# InfoAmazonia.net
KiCad netlist of a schematic drawn in EAGLE
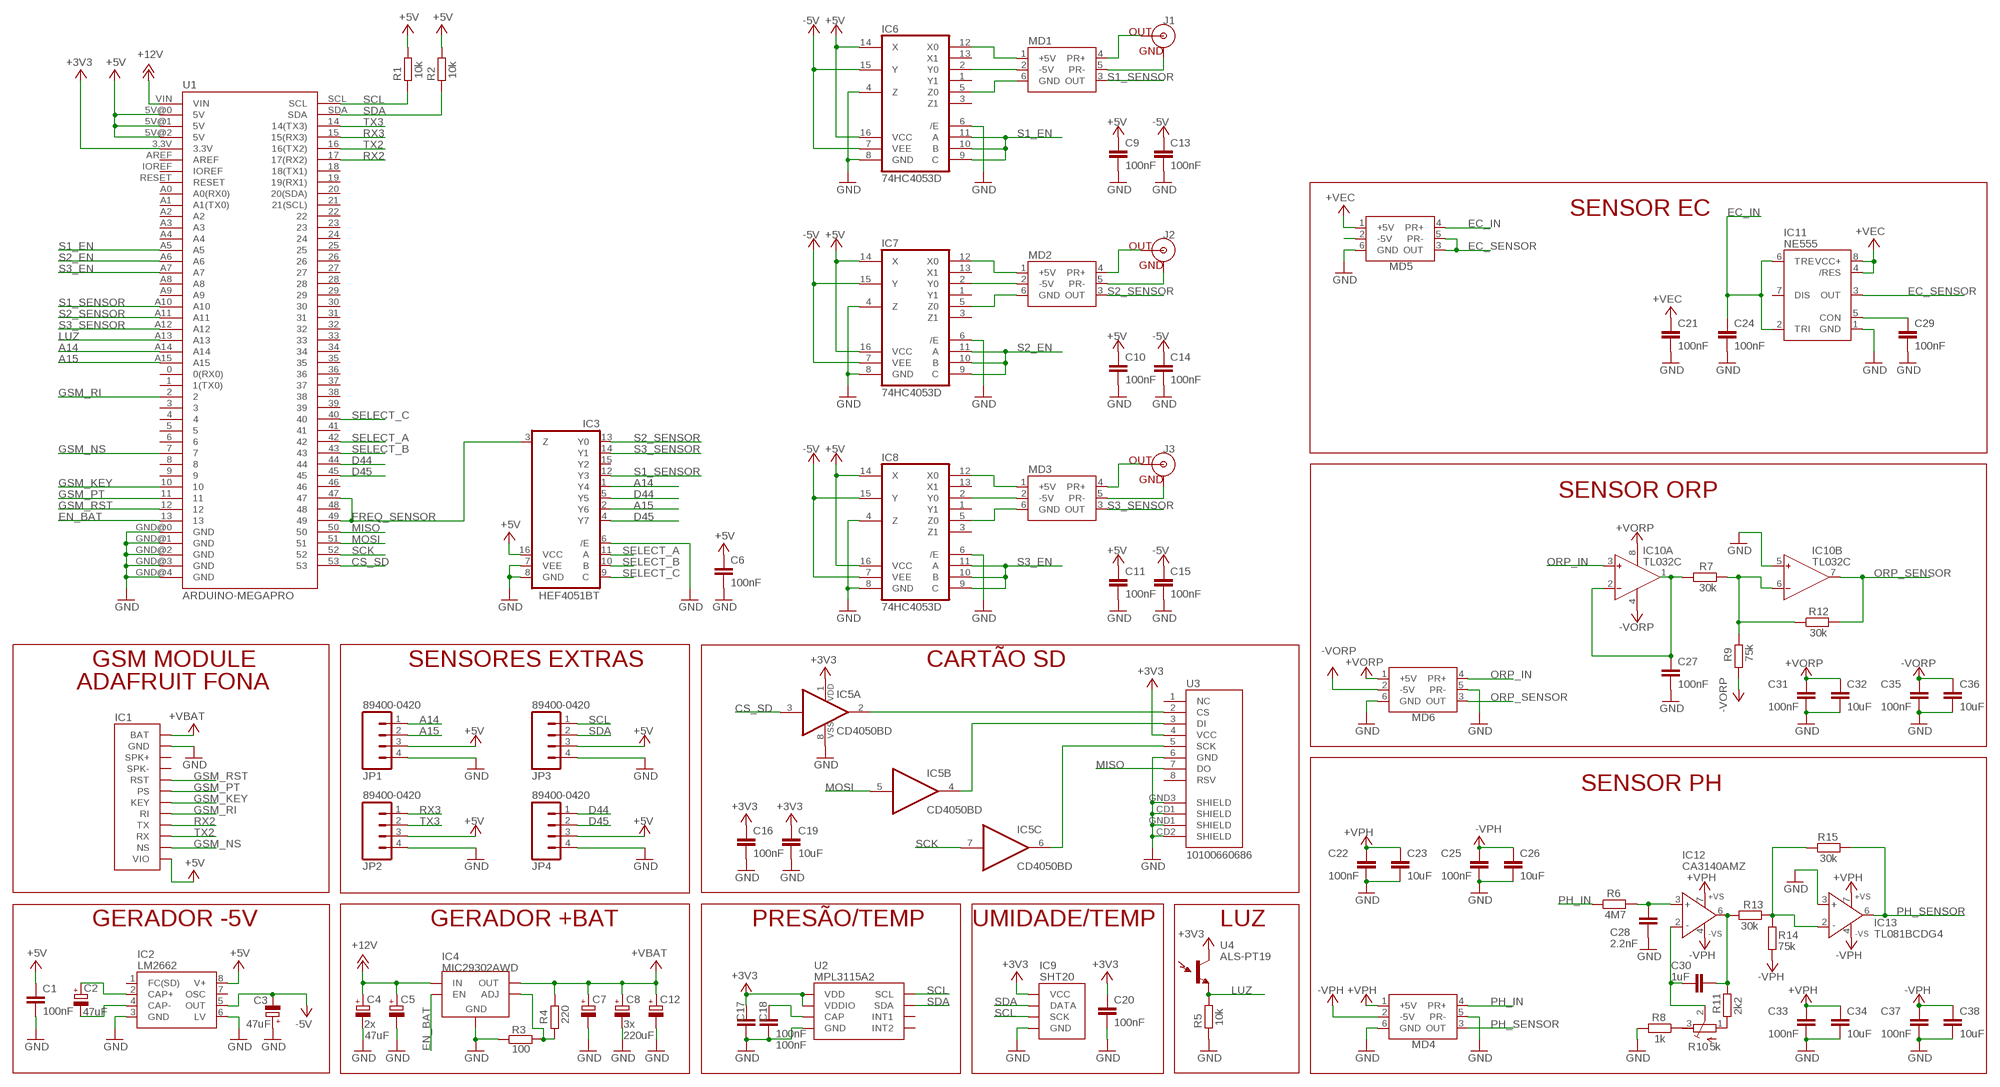
[diagram p0: schematic, sheet 1]

(export (version "E")
  (design (tool "Eeschema 10.0.6"))
  (components
    (comp (ref "C1")
      (value "100nF")
      (footprint "eagle-import:C0603")
      (libsource (lib "eagle-import") (part "C-EUC0603"))
    )
    (comp (ref "C2")
      (value "47uF")
      (footprint "eagle-import:SMC_B")
      (libsource (lib "eagle-import") (part "CPOL-EUSMC_B"))
    )
    (comp (ref "C3")
      (value "47uF")
      (footprint "eagle-import:SMC_B")
      (libsource (lib "eagle-import") (part "CPOL-EUSMC_B"))
    )
    (comp (ref "C4")
      (value "47uF")
      (footprint "eagle-import:UD-6,3X5,8_NICHICON")
      (libsource (lib "eagle-import") (part "CPOL-EUUD6,3-5,8"))
    )
    (comp (ref "C5")
      (value "47uF")
      (footprint "eagle-import:UD-6,3X5,8_NICHICON")
      (libsource (lib "eagle-import") (part "CPOL-EUUD6,3-5,8"))
    )
    (comp (ref "C6")
      (value "100nF")
      (footprint "eagle-import:C0603")
      (libsource (lib "eagle-import") (part "C-EUC0603"))
    )
    (comp (ref "C7")
      (value "220uF")
      (footprint "eagle-import:UD-6,3X5,8_NICHICON")
      (libsource (lib "eagle-import") (part "CPOL-EUUD6,3-5,8"))
    )
    (comp (ref "C8")
      (value "220uF")
      (footprint "eagle-import:UD-6,3X5,8_NICHICON")
      (libsource (lib "eagle-import") (part "CPOL-EUUD6,3-5,8"))
    )
    (comp (ref "C9")
      (value "100nF")
      (footprint "eagle-import:C0603")
      (libsource (lib "eagle-import") (part "C-EUC0603"))
    )
    (comp (ref "C10")
      (value "100nF")
      (footprint "eagle-import:C0603")
      (libsource (lib "eagle-import") (part "C-EUC0603"))
    )
    (comp (ref "C11")
      (value "100nF")
      (footprint "eagle-import:C0603")
      (libsource (lib "eagle-import") (part "C-EUC0603"))
    )
    (comp (ref "C12")
      (value "220uF")
      (footprint "eagle-import:UD-6,3X5,8_NICHICON")
      (libsource (lib "eagle-import") (part "CPOL-EUUD6,3-5,8"))
    )
    (comp (ref "C13")
      (value "100nF")
      (footprint "eagle-import:C0603")
      (libsource (lib "eagle-import") (part "C-EUC0603"))
    )
    (comp (ref "C14")
      (value "100nF")
      (footprint "eagle-import:C0603")
      (libsource (lib "eagle-import") (part "C-EUC0603"))
    )
    (comp (ref "C15")
      (value "100nF")
      (footprint "eagle-import:C0603")
      (libsource (lib "eagle-import") (part "C-EUC0603"))
    )
    (comp (ref "C16")
      (value "100nF")
      (footprint "eagle-import:C0603")
      (libsource (lib "eagle-import") (part "C-EUC0603"))
    )
    (comp (ref "C17")
      (value "100nF")
      (footprint "eagle-import:C0603")
      (libsource (lib "eagle-import") (part "C-EUC0603"))
    )
    (comp (ref "C18")
      (value "100nF")
      (footprint "eagle-import:C0603")
      (libsource (lib "eagle-import") (part "C-EUC0603"))
    )
    (comp (ref "C19")
      (value "10uF")
      (footprint "eagle-import:C0603")
      (libsource (lib "eagle-import") (part "C-EUC0603"))
    )
    (comp (ref "C20")
      (value "100nF")
      (footprint "eagle-import:C0603")
      (libsource (lib "eagle-import") (part "C-EUC0603"))
    )
    (comp (ref "C21")
      (value "100nF")
      (footprint "eagle-import:C0603")
      (libsource (lib "eagle-import") (part "C-EUC0603"))
    )
    (comp (ref "C22")
      (value "100nF")
      (footprint "eagle-import:C0603")
      (libsource (lib "eagle-import") (part "C-EUC0603"))
    )
    (comp (ref "C23")
      (value "10uF")
      (footprint "eagle-import:C0603")
      (libsource (lib "eagle-import") (part "C-EUC0603"))
    )
    (comp (ref "C24")
      (value "100nF")
      (footprint "eagle-import:C0603")
      (libsource (lib "eagle-import") (part "C-EUC0603"))
    )
    (comp (ref "C25")
      (value "100nF")
      (footprint "eagle-import:C0603")
      (libsource (lib "eagle-import") (part "C-EUC0603"))
    )
    (comp (ref "C26")
      (value "10uF")
      (footprint "eagle-import:C0603")
      (libsource (lib "eagle-import") (part "C-EUC0603"))
    )
    (comp (ref "C27")
      (value "100nF")
      (footprint "eagle-import:C0603")
      (libsource (lib "eagle-import") (part "C-EUC0603"))
    )
    (comp (ref "C28")
      (value "2.2nF")
      (footprint "eagle-import:C0603")
      (libsource (lib "eagle-import") (part "C-EUC0603"))
    )
    (comp (ref "C29")
      (value "100nF")
      (footprint "eagle-import:C0603")
      (libsource (lib "eagle-import") (part "C-EUC0603"))
    )
    (comp (ref "C30")
      (value "1uF")
      (footprint "eagle-import:C0603")
      (libsource (lib "eagle-import") (part "C-EUC0603"))
    )
    (comp (ref "C31")
      (value "100nF")
      (footprint "eagle-import:C0603")
      (libsource (lib "eagle-import") (part "C-EUC0603"))
    )
    (comp (ref "C32")
      (value "10uF")
      (footprint "eagle-import:C0603")
      (libsource (lib "eagle-import") (part "C-EUC0603"))
    )
    (comp (ref "C33")
      (value "100nF")
      (footprint "eagle-import:C0603")
      (libsource (lib "eagle-import") (part "C-EUC0603"))
    )
    (comp (ref "C34")
      (value "10uF")
      (footprint "eagle-import:C0603")
      (libsource (lib "eagle-import") (part "C-EUC0603"))
    )
    (comp (ref "C35")
      (value "100nF")
      (footprint "eagle-import:C0603")
      (libsource (lib "eagle-import") (part "C-EUC0603"))
    )
    (comp (ref "C36")
      (value "10uF")
      (footprint "eagle-import:C0603")
      (libsource (lib "eagle-import") (part "C-EUC0603"))
    )
    (comp (ref "C37")
      (value "100nF")
      (footprint "eagle-import:C0603")
      (libsource (lib "eagle-import") (part "C-EUC0603"))
    )
    (comp (ref "C38")
      (value "10uF")
      (footprint "eagle-import:C0603")
      (libsource (lib "eagle-import") (part "C-EUC0603"))
    )
    (comp (ref "IC1")
      (value "ADAFRUIT FONA")
      (footprint "eagle-import:ADAFRUIT_FONA")
      (libsource (lib "eagle-import") (part "ADAFRUIT_FONA"))
    )
    (comp (ref "IC2")
      (value "LM2662")
      (footprint "eagle-import:SO8")
      (libsource (lib "eagle-import") (part "LM2662"))
    )
    (comp (ref "IC3")
      (value "HEF4051BT")
      (footprint "eagle-import:SO16")
      (libsource (lib "eagle-import") (part "4051D"))
    )
    (comp (ref "IC4")
      (value "MIC29302AWD")
      (footprint "eagle-import:TO252-5")
      (libsource (lib "eagle-import") (part "MIC29XXX"))
    )
    (comp (ref "IC5")
      (value "CD4050BD")
      (footprint "eagle-import:SO16")
      (libsource (lib "eagle-import") (part "4050D"))
    )
    (comp (ref "IC6")
      (value "74HC4053D")
      (footprint "eagle-import:SO16")
      (libsource (lib "eagle-import") (part "4053D"))
    )
    (comp (ref "IC7")
      (value "74HC4053D")
      (footprint "eagle-import:SO16")
      (libsource (lib "eagle-import") (part "4053D"))
    )
    (comp (ref "IC8")
      (value "74HC4053D")
      (footprint "eagle-import:SO16")
      (libsource (lib "eagle-import") (part "4053D"))
    )
    (comp (ref "IC9")
      (value "SHT20")
      (footprint "eagle-import:SHT2X")
      (libsource (lib "eagle-import") (part "SHT2X"))
    )
    (comp (ref "IC10")
      (value "TL032C")
      (footprint "eagle-import:SO8")
      (fields (field (name "MF") "ALTERA CORPORATION") (field (name "MPN") "AD712KRZ"))
      (libsource (lib "eagle-import") (part "AMPOP_2R"))
    )
    (comp (ref "IC11")
      (value "NE555")
      (footprint "eagle-import:SO8")
      (libsource (lib "eagle-import") (part "NE555"))
    )
    (comp (ref "IC12")
      (value "CA3140AMZ")
      (footprint "eagle-import:SO8")
      (fields (field (name "MF") "ALTERA CORPORATION") (field (name "MPN") "AD811JRZ"))
      (libsource (lib "eagle-import") (part "AMPOP"))
    )
    (comp (ref "IC13")
      (value "TL081BCDG4")
      (footprint "eagle-import:SO8")
      (fields (field (name "MF") "ALTERA CORPORATION") (field (name "MPN") "AD811JRZ"))
      (libsource (lib "eagle-import") (part "AMPOP"))
    )
    (comp (ref "J1")
      (value "31-5431-10RFX")
      (footprint "eagle-import:BNC")
      (libsource (lib "eagle-import") (part "BNCPTH"))
    )
    (comp (ref "J2")
      (value "31-5431-10RFX")
      (footprint "eagle-import:BNC")
      (libsource (lib "eagle-import") (part "BNCPTH"))
    )
    (comp (ref "J3")
      (value "31-5431-10RFX")
      (footprint "eagle-import:BNC")
      (libsource (lib "eagle-import") (part "BNCPTH"))
    )
    (comp (ref "JP1")
      (value "89400-0420")
      (footprint "eagle-import:JST-4-PTH-VERT")
      (libsource (lib "eagle-import") (part "M04JST-PTH-VERT"))
    )
    (comp (ref "JP2")
      (value "89400-0420")
      (footprint "eagle-import:JST-4-PTH-VERT")
      (libsource (lib "eagle-import") (part "M04JST-PTH-VERT"))
    )
    (comp (ref "JP3")
      (value "89400-0420")
      (footprint "eagle-import:JST-4-PTH-VERT")
      (libsource (lib "eagle-import") (part "M04JST-PTH-VERT"))
    )
    (comp (ref "JP4")
      (value "89400-0420")
      (footprint "eagle-import:JST-4-PTH-VERT")
      (libsource (lib "eagle-import") (part "M04JST-PTH-VERT"))
    )
    (comp (ref "MD1")
      (value "INFO-AMAZONIA-MODULE")
      (footprint "eagle-import:INFO-AMAZONIA-MODULE")
      (libsource (lib "eagle-import") (part "INFO-AMAZONIA-MODULE"))
    )
    (comp (ref "MD2")
      (value "INFO-AMAZONIA-MODULE")
      (footprint "eagle-import:INFO-AMAZONIA-MODULE")
      (libsource (lib "eagle-import") (part "INFO-AMAZONIA-MODULE"))
    )
    (comp (ref "MD3")
      (value "INFO-AMAZONIA-MODULE")
      (footprint "eagle-import:INFO-AMAZONIA-MODULE")
      (libsource (lib "eagle-import") (part "INFO-AMAZONIA-MODULE"))
    )
    (comp (ref "MD4")
      (value "INFO-AMAZONIA-MODULE")
      (footprint "eagle-import:INFO-AMAZONIA-MODULE")
      (libsource (lib "eagle-import") (part "INFO-AMAZONIA-MODULE"))
    )
    (comp (ref "MD5")
      (value "INFO-AMAZONIA-MODULE")
      (footprint "eagle-import:INFO-AMAZONIA-MODULE")
      (libsource (lib "eagle-import") (part "INFO-AMAZONIA-MODULE"))
    )
    (comp (ref "MD6")
      (value "INFO-AMAZONIA-MODULE")
      (footprint "eagle-import:INFO-AMAZONIA-MODULE")
      (libsource (lib "eagle-import") (part "INFO-AMAZONIA-MODULE"))
    )
    (comp (ref "R1")
      (value "10k")
      (footprint "eagle-import:R0603")
      (libsource (lib "eagle-import") (part "R-EU_R0603"))
    )
    (comp (ref "R2")
      (value "10k")
      (footprint "eagle-import:R0603")
      (libsource (lib "eagle-import") (part "R-EU_R0603"))
    )
    (comp (ref "R3")
      (value "100")
      (footprint "eagle-import:R0603")
      (libsource (lib "eagle-import") (part "R-EU_R0603"))
    )
    (comp (ref "R4")
      (value "220")
      (footprint "eagle-import:R0603")
      (libsource (lib "eagle-import") (part "R-EU_R0603"))
    )
    (comp (ref "R5")
      (value "10k")
      (footprint "eagle-import:R0603")
      (libsource (lib "eagle-import") (part "R-EU_R0603"))
    )
    (comp (ref "R6")
      (value "4M7")
      (footprint "eagle-import:R0603")
      (libsource (lib "eagle-import") (part "R-EU_R0603"))
    )
    (comp (ref "R7")
      (value "30k")
      (footprint "eagle-import:R0603")
      (libsource (lib "eagle-import") (part "R-EU_R0603"))
    )
    (comp (ref "R8")
      (value "1k")
      (footprint "eagle-import:R0603")
      (libsource (lib "eagle-import") (part "R-EU_R0603"))
    )
    (comp (ref "R9")
      (value "75k")
      (footprint "eagle-import:R0603")
      (libsource (lib "eagle-import") (part "R-EU_R0603"))
    )
    (comp (ref "R10")
      (value "5k")
      (footprint "eagle-import:RTRIM3296W")
      (libsource (lib "eagle-import") (part "RTRIM329W"))
    )
    (comp (ref "R11")
      (value "2k2")
      (footprint "eagle-import:R0603")
      (libsource (lib "eagle-import") (part "R-EU_R0603"))
    )
    (comp (ref "R12")
      (value "30k")
      (footprint "eagle-import:R0603")
      (libsource (lib "eagle-import") (part "R-EU_R0603"))
    )
    (comp (ref "R13")
      (value "30k")
      (footprint "eagle-import:R0603")
      (libsource (lib "eagle-import") (part "R-EU_R0603"))
    )
    (comp (ref "R14")
      (value "75k")
      (footprint "eagle-import:R0603")
      (libsource (lib "eagle-import") (part "R-EU_R0603"))
    )
    (comp (ref "R15")
      (value "30k")
      (footprint "eagle-import:R0603")
      (libsource (lib "eagle-import") (part "R-EU_R0603"))
    )
    (comp (ref "U1")
      (value "ARDUINO-MEGAPRO")
      (footprint "eagle-import:ARDUINO_MEGA_2560")
      (libsource (lib "eagle-import") (part "ARDUINO-MEGAPRO"))
    )
    (comp (ref "U2")
      (value "MPL3115A2")
      (footprint "eagle-import:LGA8")
      (libsource (lib "eagle-import") (part "MPL3115A2LGA8"))
    )
    (comp (ref "U3")
      (value "10100660686")
      (footprint "eagle-import:MICRO-SD-SOCKET-PP")
      (libsource (lib "eagle-import") (part "USD-SOCKETNEW"))
    )
    (comp (ref "U4")
      (value "ALS-PT19")
      (footprint "eagle-import:ALS-PT19")
      (libsource (lib "eagle-import") (part "LIGHTSENSORALS"))
    )
  )
  (nets
    (net (code "1") (name "+3V3") (class "Default")
      (node (ref "C16") (pin "1") (pinfunction "1_1") (pintype "passive"))
      (node (ref "C17") (pin "1") (pinfunction "1_1") (pintype "passive"))
      (node (ref "C19") (pin "1") (pinfunction "1_1") (pintype "passive"))
      (node (ref "C20") (pin "1") (pinfunction "1_1") (pintype "passive"))
      (node (ref "IC5") (pin "1") (pinfunction "VDD_1") (pintype "power_in"))
      (node (ref "IC9") (pin "5") (pinfunction "VCC_5") (pintype "power_in"))
      (node (ref "U1") (pin "3.3V") (pinfunction "3.3V_3.3V") (pintype "bidirectional"))
      (node (ref "U2") (pin "1") (pinfunction "VDD_1") (pintype "power_in"))
      (node (ref "U2") (pin "4") (pinfunction "VDDIO_4") (pintype "power_in"))
      (node (ref "U3") (pin "4") (pinfunction "VCC_4") (pintype "bidirectional"))
      (node (ref "U4") (pin "C") (pinfunction "C1_C") (pintype "passive"))
    )
    (net (code "2") (name "+5V") (class "Default")
      (node (ref "C1") (pin "1") (pinfunction "1_1") (pintype "passive"))
      (node (ref "C10") (pin "1") (pinfunction "1_1") (pintype "passive"))
      (node (ref "C11") (pin "1") (pinfunction "1_1") (pintype "passive"))
      (node (ref "C6") (pin "1") (pinfunction "1_1") (pintype "passive"))
      (node (ref "C9") (pin "1") (pinfunction "1_1") (pintype "passive"))
      (node (ref "IC1") (pin "12") (pinfunction "VIO_12") (pintype "bidirectional"))
      (node (ref "IC2") (pin "8") (pinfunction "V+_8") (pintype "bidirectional"))
      (node (ref "IC3") (pin "16") (pinfunction "VCC_16") (pintype "bidirectional"))
      (node (ref "IC6") (pin "14") (pinfunction "X_14") (pintype "bidirectional"))
      (node (ref "IC6") (pin "16") (pinfunction "VCC_16") (pintype "bidirectional"))
      (node (ref "IC7") (pin "14") (pinfunction "X_14") (pintype "bidirectional"))
      (node (ref "IC7") (pin "16") (pinfunction "VCC_16") (pintype "bidirectional"))
      (node (ref "IC8") (pin "14") (pinfunction "X_14") (pintype "bidirectional"))
      (node (ref "IC8") (pin "16") (pinfunction "VCC_16") (pintype "bidirectional"))
      (node (ref "JP1") (pin "3") (pinfunction "3_3") (pintype "passive"))
      (node (ref "JP2") (pin "3") (pinfunction "3_3") (pintype "passive"))
      (node (ref "JP3") (pin "3") (pinfunction "3_3") (pintype "passive"))
      (node (ref "JP4") (pin "3") (pinfunction "3_3") (pintype "passive"))
      (node (ref "R1") (pin "2") (pinfunction "2_2") (pintype "passive"))
      (node (ref "R2") (pin "2") (pinfunction "2_2") (pintype "passive"))
      (node (ref "U1") (pin "5V@0") (pinfunction "5V_5V@0") (pintype "bidirectional"))
      (node (ref "U1") (pin "5V@1") (pinfunction "5V_5V@1") (pintype "bidirectional"))
      (node (ref "U1") (pin "5V@2") (pinfunction "5V_5V@2") (pintype "bidirectional"))
    )
    (net (code "3") (name "+12V") (class "Default")
      (node (ref "C4") (pin "+") (pinfunction "+_+") (pintype "passive"))
      (node (ref "C5") (pin "+") (pinfunction "+_+") (pintype "passive"))
      (node (ref "IC4") (pin "2") (pinfunction "IN_2") (pintype "bidirectional"))
      (node (ref "U1") (pin "VIN") (pinfunction "VIN_VIN") (pintype "bidirectional"))
    )
    (net (code "4") (name "+VBAT") (class "Default")
      (node (ref "C12") (pin "+") (pinfunction "+_+") (pintype "passive"))
      (node (ref "C7") (pin "+") (pinfunction "+_+") (pintype "passive"))
      (node (ref "C8") (pin "+") (pinfunction "+_+") (pintype "passive"))
      (node (ref "IC1") (pin "1") (pinfunction "BAT_1") (pintype "bidirectional"))
      (node (ref "IC4") (pin "4") (pinfunction "OUT_4") (pintype "bidirectional"))
      (node (ref "R4") (pin "1") (pinfunction "1_1") (pintype "passive"))
    )
    (net (code "5") (name "+VEC") (class "Default")
      (node (ref "C21") (pin "1") (pinfunction "1_1") (pintype "passive"))
      (node (ref "IC11") (pin "4") (pinfunction "/RES_4") (pintype "input"))
      (node (ref "IC11") (pin "8") (pinfunction "VCC+_8") (pintype "power_in"))
      (node (ref "MD5") (pin "1") (pinfunction "+5V_1") (pintype "power_in"))
    )
    (net (code "6") (name "+VORP") (class "Default")
      (node (ref "C31") (pin "1") (pinfunction "1_1") (pintype "passive"))
      (node (ref "C32") (pin "1") (pinfunction "1_1") (pintype "passive"))
      (node (ref "IC10") (pin "8") (pinfunction "V+_8") (pintype "power_in"))
      (node (ref "MD6") (pin "1") (pinfunction "+5V_1") (pintype "power_in"))
    )
    (net (code "7") (name "+VPH") (class "Default")
      (node (ref "C22") (pin "1") (pinfunction "1_1") (pintype "passive"))
      (node (ref "C23") (pin "1") (pinfunction "1_1") (pintype "passive"))
      (node (ref "C33") (pin "1") (pinfunction "1_1") (pintype "passive"))
      (node (ref "C34") (pin "1") (pinfunction "1_1") (pintype "passive"))
      (node (ref "IC12") (pin "7") (pinfunction "+VS_7") (pintype "input"))
      (node (ref "IC13") (pin "7") (pinfunction "+VS_7") (pintype "input"))
      (node (ref "MD4") (pin "1") (pinfunction "+5V_1") (pintype "power_in"))
    )
    (net (code "8") (name "-5V") (class "Default")
      (node (ref "C13") (pin "1") (pinfunction "1_1") (pintype "passive"))
      (node (ref "C14") (pin "1") (pinfunction "1_1") (pintype "passive"))
      (node (ref "C15") (pin "1") (pinfunction "1_1") (pintype "passive"))
      (node (ref "C3") (pin "-") (pinfunction "-_-") (pintype "passive"))
      (node (ref "IC2") (pin "5") (pinfunction "OUT_5") (pintype "input"))
      (node (ref "IC6") (pin "15") (pinfunction "Y_15") (pintype "bidirectional"))
      (node (ref "IC6") (pin "7") (pinfunction "VEE_7") (pintype "bidirectional"))
      (node (ref "IC7") (pin "15") (pinfunction "Y_15") (pintype "bidirectional"))
      (node (ref "IC7") (pin "7") (pinfunction "VEE_7") (pintype "bidirectional"))
      (node (ref "IC8") (pin "15") (pinfunction "Y_15") (pintype "bidirectional"))
      (node (ref "IC8") (pin "7") (pinfunction "VEE_7") (pintype "bidirectional"))
    )
    (net (code "9") (name "-VORP") (class "Default")
      (node (ref "C35") (pin "1") (pinfunction "1_1") (pintype "passive"))
      (node (ref "C36") (pin "1") (pinfunction "1_1") (pintype "passive"))
      (node (ref "IC10") (pin "4") (pinfunction "V-_4") (pintype "power_in"))
      (node (ref "MD6") (pin "2") (pinfunction "-5V_2") (pintype "power_in"))
      (node (ref "R9") (pin "2") (pinfunction "2_2") (pintype "passive"))
    )
    (net (code "10") (name "-VPH") (class "Default")
      (node (ref "C25") (pin "1") (pinfunction "1_1") (pintype "passive"))
      (node (ref "C26") (pin "1") (pinfunction "1_1") (pintype "passive"))
      (node (ref "C37") (pin "1") (pinfunction "1_1") (pintype "passive"))
      (node (ref "C38") (pin "1") (pinfunction "1_1") (pintype "passive"))
      (node (ref "IC12") (pin "4") (pinfunction "-VS_4") (pintype "input"))
      (node (ref "IC13") (pin "4") (pinfunction "-VS_4") (pintype "input"))
      (node (ref "MD4") (pin "2") (pinfunction "-5V_2") (pintype "power_in"))
      (node (ref "R14") (pin "2") (pinfunction "2_2") (pintype "passive"))
    )
    (net (code "11") (name "/A14") (class "Default")
      (node (ref "IC3") (pin "1") (pinfunction "Y4_1") (pintype "bidirectional"))
      (node (ref "JP1") (pin "1") (pinfunction "1_1") (pintype "passive"))
      (node (ref "U1") (pin "A14") (pinfunction "A14_A14") (pintype "bidirectional"))
    )
    (net (code "12") (name "/A15") (class "Default")
      (node (ref "IC3") (pin "2") (pinfunction "Y6_2") (pintype "bidirectional"))
      (node (ref "JP1") (pin "2") (pinfunction "2_2") (pintype "passive"))
      (node (ref "U1") (pin "A15") (pinfunction "A15_A15") (pintype "bidirectional"))
    )
    (net (code "13") (name "/CS_SD") (class "Default")
      (node (ref "IC5") (pin "3") (pinfunction "I_3") (pintype "input"))
      (node (ref "U1") (pin "53") (pinfunction "53_53") (pintype "bidirectional"))
    )
    (net (code "14") (name "/D44") (class "Default")
      (node (ref "IC3") (pin "5") (pinfunction "Y5_5") (pintype "bidirectional"))
      (node (ref "JP4") (pin "1") (pinfunction "1_1") (pintype "passive"))
      (node (ref "U1") (pin "44") (pinfunction "44_44") (pintype "bidirectional"))
    )
    (net (code "15") (name "/D45") (class "Default")
      (node (ref "IC3") (pin "4") (pinfunction "Y7_4") (pintype "bidirectional"))
      (node (ref "JP4") (pin "2") (pinfunction "2_2") (pintype "passive"))
      (node (ref "U1") (pin "45") (pinfunction "45_45") (pintype "bidirectional"))
    )
    (net (code "16") (name "/EC_IN") (class "Default")
      (node (ref "C24") (pin "1") (pinfunction "1_1") (pintype "passive"))
      (node (ref "IC11") (pin "2") (pinfunction "TRI_2") (pintype "input"))
      (node (ref "IC11") (pin "6") (pinfunction "TRE_6") (pintype "input"))
      (node (ref "MD5") (pin "4") (pinfunction "PR+_4") (pintype "bidirectional"))
    )
    (net (code "17") (name "/EC_SENSOR") (class "Default")
      (node (ref "IC11") (pin "3") (pinfunction "OUT_3") (pintype "output"))
      (node (ref "MD5") (pin "3") (pinfunction "OUT_3") (pintype "output"))
      (node (ref "MD5") (pin "5") (pinfunction "PR-_5") (pintype "input"))
    )
    (net (code "18") (name "/EN_BAT") (class "Default")
      (node (ref "IC4") (pin "1") (pinfunction "EN_1") (pintype "bidirectional"))
      (node (ref "U1") (pin "13") (pinfunction "13_13") (pintype "bidirectional"))
    )
    (net (code "19") (name "/FC(SD)") (class "Default")
      (node (ref "IC2") (pin "1") (pinfunction "FC(SD)_1") (pintype "power_in"))
    )
    (net (code "20") (name "/FREQ_SENSOR") (class "Default")
      (node (ref "IC3") (pin "3") (pinfunction "Z_3") (pintype "bidirectional"))
      (node (ref "U1") (pin "47") (pinfunction "47_47") (pintype "bidirectional"))
      (node (ref "U1") (pin "49") (pinfunction "49_49") (pintype "bidirectional"))
    )
    (net (code "21") (name "/GSM_KEY") (class "Default")
      (node (ref "IC1") (pin "7") (pinfunction "KEY_7") (pintype "bidirectional"))
      (node (ref "U1") (pin "10") (pinfunction "10_10") (pintype "bidirectional"))
    )
    (net (code "22") (name "/GSM_NS") (class "Default")
      (node (ref "IC1") (pin "11") (pinfunction "NS_11") (pintype "bidirectional"))
      (node (ref "U1") (pin "7") (pinfunction "7_7") (pintype "bidirectional"))
    )
    (net (code "23") (name "/GSM_PT") (class "Default")
      (node (ref "IC1") (pin "6") (pinfunction "PS_6") (pintype "bidirectional"))
      (node (ref "U1") (pin "11") (pinfunction "11_11") (pintype "bidirectional"))
    )
    (net (code "24") (name "/GSM_RI") (class "Default")
      (node (ref "IC1") (pin "8") (pinfunction "RI_8") (pintype "bidirectional"))
      (node (ref "U1") (pin "2") (pinfunction "2_2") (pintype "bidirectional"))
    )
    (net (code "25") (name "/GSM_RST") (class "Default")
      (node (ref "IC1") (pin "5") (pinfunction "RST_5") (pintype "bidirectional"))
      (node (ref "U1") (pin "12") (pinfunction "12_12") (pintype "bidirectional"))
    )
    (net (code "26") (name "/LUZ") (class "Default")
      (node (ref "R5") (pin "2") (pinfunction "2_2") (pintype "passive"))
      (node (ref "U1") (pin "A13") (pinfunction "A13_A13") (pintype "bidirectional"))
      (node (ref "U4") (pin "E") (pinfunction "E1_E") (pintype "passive"))
    )
    (net (code "27") (name "/MISO") (class "Default")
      (node (ref "U1") (pin "50") (pinfunction "50_50") (pintype "bidirectional"))
      (node (ref "U3") (pin "7") (pinfunction "DO_7") (pintype "bidirectional"))
    )
    (net (code "28") (name "/MOSI") (class "Default")
      (node (ref "IC5") (pin "5") (pinfunction "I_5") (pintype "input"))
      (node (ref "U1") (pin "51") (pinfunction "51_51") (pintype "bidirectional"))
    )
    (net (code "29") (name "/ORP_IN") (class "Default")
      (node (ref "IC10") (pin "3") (pinfunction "IN+_3") (pintype "input"))
      (node (ref "MD6") (pin "4") (pinfunction "PR+_4") (pintype "bidirectional"))
    )
    (net (code "30") (name "/ORP_SENSOR") (class "Default")
      (node (ref "IC10") (pin "7") (pinfunction "OUT_7") (pintype "output"))
      (node (ref "MD6") (pin "3") (pinfunction "OUT_3") (pintype "output"))
      (node (ref "R12") (pin "2") (pinfunction "2_2") (pintype "passive"))
    )
    (net (code "31") (name "/PH_IN") (class "Default")
      (node (ref "MD4") (pin "4") (pinfunction "PR+_4") (pintype "bidirectional"))
      (node (ref "R6") (pin "1") (pinfunction "1_1") (pintype "passive"))
    )
    (net (code "32") (name "/PH_SENSOR") (class "Default")
      (node (ref "IC13") (pin "6") (pinfunction "OUT_6") (pintype "output"))
      (node (ref "MD4") (pin "3") (pinfunction "OUT_3") (pintype "output"))
      (node (ref "R15") (pin "2") (pinfunction "2_2") (pintype "passive"))
    )
    (net (code "33") (name "/RX2") (class "Default")
      (node (ref "IC1") (pin "9") (pinfunction "TX_9") (pintype "bidirectional"))
      (node (ref "U1") (pin "17") (pinfunction "17(RX2)_17") (pintype "bidirectional"))
    )
    (net (code "34") (name "/RX3") (class "Default")
      (node (ref "JP2") (pin "1") (pinfunction "1_1") (pintype "passive"))
      (node (ref "U1") (pin "15") (pinfunction "15(RX3)_15") (pintype "bidirectional"))
    )
    (net (code "35") (name "/S1_EN") (class "Default")
      (node (ref "IC6") (pin "10") (pinfunction "B_10") (pintype "input"))
      (node (ref "IC6") (pin "11") (pinfunction "A_11") (pintype "input"))
      (node (ref "IC6") (pin "9") (pinfunction "C_9") (pintype "input"))
      (node (ref "U1") (pin "A5") (pinfunction "A5_A5") (pintype "bidirectional"))
    )
    (net (code "36") (name "/S1_SENSOR") (class "Default")
      (node (ref "IC3") (pin "12") (pinfunction "Y3_12") (pintype "bidirectional"))
      (node (ref "MD1") (pin "3") (pinfunction "OUT_3") (pintype "output"))
      (node (ref "U1") (pin "A10") (pinfunction "A10_A10") (pintype "bidirectional"))
    )
    (net (code "37") (name "/S2_EN") (class "Default")
      (node (ref "IC7") (pin "10") (pinfunction "B_10") (pintype "input"))
      (node (ref "IC7") (pin "11") (pinfunction "A_11") (pintype "input"))
      (node (ref "IC7") (pin "9") (pinfunction "C_9") (pintype "input"))
      (node (ref "U1") (pin "A6") (pinfunction "A6_A6") (pintype "bidirectional"))
    )
    (net (code "38") (name "/S2_SENSOR") (class "Default")
      (node (ref "IC3") (pin "13") (pinfunction "Y0_13") (pintype "bidirectional"))
      (node (ref "MD2") (pin "3") (pinfunction "OUT_3") (pintype "output"))
      (node (ref "U1") (pin "A11") (pinfunction "A11_A11") (pintype "bidirectional"))
    )
    (net (code "39") (name "/S3_EN") (class "Default")
      (node (ref "IC8") (pin "10") (pinfunction "B_10") (pintype "input"))
      (node (ref "IC8") (pin "11") (pinfunction "A_11") (pintype "input"))
      (node (ref "IC8") (pin "9") (pinfunction "C_9") (pintype "input"))
      (node (ref "U1") (pin "A7") (pinfunction "A7_A7") (pintype "bidirectional"))
    )
    (net (code "40") (name "/S3_SENSOR") (class "Default")
      (node (ref "IC3") (pin "14") (pinfunction "Y1_14") (pintype "bidirectional"))
      (node (ref "MD3") (pin "3") (pinfunction "OUT_3") (pintype "output"))
      (node (ref "U1") (pin "A12") (pinfunction "A12_A12") (pintype "bidirectional"))
    )
    (net (code "41") (name "/SCK") (class "Default")
      (node (ref "IC5") (pin "7") (pinfunction "I_7") (pintype "input"))
      (node (ref "U1") (pin "52") (pinfunction "52_52") (pintype "bidirectional"))
    )
    (net (code "42") (name "/SCL") (class "Default")
      (node (ref "IC9") (pin "6") (pinfunction "SCK_6") (pintype "input"))
      (node (ref "JP3") (pin "1") (pinfunction "1_1") (pintype "passive"))
      (node (ref "R1") (pin "1") (pinfunction "1_1") (pintype "passive"))
      (node (ref "U1") (pin "SCL") (pinfunction "SCL_SCL") (pintype "bidirectional"))
      (node (ref "U2") (pin "8") (pinfunction "SCL_8") (pintype "bidirectional"))
    )
    (net (code "43") (name "/SDA") (class "Default")
      (node (ref "IC9") (pin "1") (pinfunction "DATA_1") (pintype "bidirectional"))
      (node (ref "JP3") (pin "2") (pinfunction "2_2") (pintype "passive"))
      (node (ref "R2") (pin "1") (pinfunction "1_1") (pintype "passive"))
      (node (ref "U1") (pin "SDA") (pinfunction "SDA_SDA") (pintype "bidirectional"))
      (node (ref "U2") (pin "7") (pinfunction "SDA_7") (pintype "bidirectional"))
    )
    (net (code "44") (name "/SELECT_A") (class "Default")
      (node (ref "IC3") (pin "11") (pinfunction "A_11") (pintype "input"))
      (node (ref "U1") (pin "42") (pinfunction "42_42") (pintype "bidirectional"))
    )
    (net (code "45") (name "/SELECT_B") (class "Default")
      (node (ref "IC3") (pin "10") (pinfunction "B_10") (pintype "input"))
      (node (ref "U1") (pin "43") (pinfunction "43_43") (pintype "bidirectional"))
    )
    (net (code "46") (name "/SELECT_C") (class "Default")
      (node (ref "IC3") (pin "9") (pinfunction "C_9") (pintype "input"))
      (node (ref "U1") (pin "40") (pinfunction "40_40") (pintype "bidirectional"))
    )
    (net (code "47") (name "/TX2") (class "Default")
      (node (ref "IC1") (pin "10") (pinfunction "RX_10") (pintype "bidirectional"))
      (node (ref "U1") (pin "16") (pinfunction "16(TX2)_16") (pintype "bidirectional"))
    )
    (net (code "48") (name "/TX3") (class "Default")
      (node (ref "JP2") (pin "2") (pinfunction "2_2") (pintype "passive"))
      (node (ref "U1") (pin "14") (pinfunction "14(TX3)_14") (pintype "bidirectional"))
    )
    (net (code "49") (name "GND") (class "Default")
      (node (ref "C1") (pin "2") (pinfunction "2_2") (pintype "passive"))
      (node (ref "C10") (pin "2") (pinfunction "2_2") (pintype "passive"))
      (node (ref "C11") (pin "2") (pinfunction "2_2") (pintype "passive"))
      (node (ref "C12") (pin "-") (pinfunction "-_-") (pintype "passive"))
      (node (ref "C13") (pin "2") (pinfunction "2_2") (pintype "passive"))
      (node (ref "C14") (pin "2") (pinfunction "2_2") (pintype "passive"))
      (node (ref "C15") (pin "2") (pinfunction "2_2") (pintype "passive"))
      (node (ref "C16") (pin "2") (pinfunction "2_2") (pintype "passive"))
      (node (ref "C17") (pin "2") (pinfunction "2_2") (pintype "passive"))
      (node (ref "C18") (pin "2") (pinfunction "2_2") (pintype "passive"))
      (node (ref "C19") (pin "2") (pinfunction "2_2") (pintype "passive"))
      (node (ref "C20") (pin "2") (pinfunction "2_2") (pintype "passive"))
      (node (ref "C21") (pin "2") (pinfunction "2_2") (pintype "passive"))
      (node (ref "C22") (pin "2") (pinfunction "2_2") (pintype "passive"))
      (node (ref "C23") (pin "2") (pinfunction "2_2") (pintype "passive"))
      (node (ref "C24") (pin "2") (pinfunction "2_2") (pintype "passive"))
      (node (ref "C25") (pin "2") (pinfunction "2_2") (pintype "passive"))
      (node (ref "C26") (pin "2") (pinfunction "2_2") (pintype "passive"))
      (node (ref "C27") (pin "2") (pinfunction "2_2") (pintype "passive"))
      (node (ref "C28") (pin "2") (pinfunction "2_2") (pintype "passive"))
      (node (ref "C29") (pin "2") (pinfunction "2_2") (pintype "passive"))
      (node (ref "C3") (pin "+") (pinfunction "+_+") (pintype "passive"))
      (node (ref "C31") (pin "2") (pinfunction "2_2") (pintype "passive"))
      (node (ref "C32") (pin "2") (pinfunction "2_2") (pintype "passive"))
      (node (ref "C33") (pin "2") (pinfunction "2_2") (pintype "passive"))
      (node (ref "C34") (pin "2") (pinfunction "2_2") (pintype "passive"))
      (node (ref "C35") (pin "2") (pinfunction "2_2") (pintype "passive"))
      (node (ref "C36") (pin "2") (pinfunction "2_2") (pintype "passive"))
      (node (ref "C37") (pin "2") (pinfunction "2_2") (pintype "passive"))
      (node (ref "C38") (pin "2") (pinfunction "2_2") (pintype "passive"))
      (node (ref "C4") (pin "-") (pinfunction "-_-") (pintype "passive"))
      (node (ref "C5") (pin "-") (pinfunction "-_-") (pintype "passive"))
      (node (ref "C6") (pin "2") (pinfunction "2_2") (pintype "passive"))
      (node (ref "C7") (pin "-") (pinfunction "-_-") (pintype "passive"))
      (node (ref "C8") (pin "-") (pinfunction "-_-") (pintype "passive"))
      (node (ref "C9") (pin "2") (pinfunction "2_2") (pintype "passive"))
      (node (ref "IC1") (pin "2") (pinfunction "GND_2") (pintype "bidirectional"))
      (node (ref "IC1") (pin "K1") (pinfunction "GND_K1") (pintype "bidirectional"))
      (node (ref "IC1") (pin "K2") (pinfunction "GND_K2") (pintype "bidirectional"))
      (node (ref "IC10") (pin "5") (pinfunction "IN+_5") (pintype "input"))
      (node (ref "IC11") (pin "1") (pinfunction "GND_1") (pintype "power_in"))
      (node (ref "IC13") (pin "3") (pinfunction "IN+_3") (pintype "input"))
      (node (ref "IC2") (pin "3") (pinfunction "GND_3") (pintype "power_in"))
      (node (ref "IC2") (pin "6") (pinfunction "LV_6") (pintype "output"))
      (node (ref "IC3") (pin "6") (pinfunction "/E_6") (pintype "input"))
      (node (ref "IC3") (pin "7") (pinfunction "VEE_7") (pintype "bidirectional"))
      (node (ref "IC3") (pin "8") (pinfunction "GND_8") (pintype "bidirectional"))
      (node (ref "IC4") (pin "3") (pinfunction "GND_3") (pintype "bidirectional"))
      (node (ref "IC4") (pin "6") (pinfunction "GND_6") (pintype "bidirectional"))
      (node (ref "IC5") (pin "8") (pinfunction "VSS_8") (pintype "power_in"))
      (node (ref "IC6") (pin "4") (pinfunction "Z_4") (pintype "bidirectional"))
      (node (ref "IC6") (pin "6") (pinfunction "/E_6") (pintype "input"))
      (node (ref "IC6") (pin "8") (pinfunction "GND_8") (pintype "bidirectional"))
      (node (ref "IC7") (pin "4") (pinfunction "Z_4") (pintype "bidirectional"))
      (node (ref "IC7") (pin "6") (pinfunction "/E_6") (pintype "input"))
      (node (ref "IC7") (pin "8") (pinfunction "GND_8") (pintype "bidirectional"))
      (node (ref "IC8") (pin "4") (pinfunction "Z_4") (pintype "bidirectional"))
      (node (ref "IC8") (pin "6") (pinfunction "/E_6") (pintype "input"))
      (node (ref "IC8") (pin "8") (pinfunction "GND_8") (pintype "bidirectional"))
      (node (ref "IC9") (pin "2") (pinfunction "GND_2") (pintype "power_in"))
      (node (ref "IC9") (pin "7") (pinfunction "GND_7") (pintype "power_in"))
      (node (ref "JP1") (pin "4") (pinfunction "4_4") (pintype "passive"))
      (node (ref "JP2") (pin "4") (pinfunction "4_4") (pintype "passive"))
      (node (ref "JP3") (pin "4") (pinfunction "4_4") (pintype "passive"))
      (node (ref "JP4") (pin "4") (pinfunction "4_4") (pintype "passive"))
      (node (ref "MD4") (pin "5") (pinfunction "PR-_5") (pintype "input"))
      (node (ref "MD4") (pin "6") (pinfunction "GND_6") (pintype "bidirectional"))
      (node (ref "MD5") (pin "6") (pinfunction "GND_6") (pintype "bidirectional"))
      (node (ref "MD6") (pin "5") (pinfunction "PR-_5") (pintype "input"))
      (node (ref "MD6") (pin "6") (pinfunction "GND_6") (pintype "bidirectional"))
      (node (ref "R3") (pin "1") (pinfunction "1_1") (pintype "passive"))
      (node (ref "R5") (pin "1") (pinfunction "1_1") (pintype "passive"))
      (node (ref "R8") (pin "2") (pinfunction "2_2") (pintype "passive"))
      (node (ref "U1") (pin "GND@0") (pinfunction "GND_GND@0") (pintype "bidirectional"))
      (node (ref "U1") (pin "GND@1") (pinfunction "GND_GND@1") (pintype "bidirectional"))
      (node (ref "U1") (pin "GND@2") (pinfunction "GND_GND@2") (pintype "bidirectional"))
      (node (ref "U1") (pin "GND@3") (pinfunction "GND_GND@3") (pintype "bidirectional"))
      (node (ref "U1") (pin "GND@4") (pinfunction "GND_GND@4") (pintype "bidirectional"))
      (node (ref "U2") (pin "3") (pinfunction "GND_3") (pintype "power_in"))
      (node (ref "U3") (pin "6") (pinfunction "GND_6") (pintype "bidirectional"))
      (node (ref "U3") (pin "CD1") (pinfunction "SHIELD_CD1") (pintype "bidirectional"))
      (node (ref "U3") (pin "CD2") (pinfunction "SHIELD_CD2") (pintype "bidirectional"))
      (node (ref "U3") (pin "GND1") (pinfunction "SHIELD_GND1") (pintype "bidirectional"))
      (node (ref "U3") (pin "GND3") (pinfunction "SHIELD_GND3") (pintype "bidirectional"))
    )
    (net (code "50") (name "Net-(IC2-CAP+)") (class "Default")
      (node (ref "C2") (pin "+") (pinfunction "+_+") (pintype "passive"))
      (node (ref "IC2") (pin "2") (pinfunction "CAP+_2") (pintype "power_in"))
    )
    (net (code "51") (name "Net-(IC2-CAP-)") (class "Default")
      (node (ref "C2") (pin "-") (pinfunction "-_-") (pintype "passive"))
      (node (ref "IC2") (pin "4") (pinfunction "CAP-_4") (pintype "bidirectional"))
    )
    (net (code "52") (name "Net-(IC4-ADJ)") (class "Default")
      (node (ref "IC4") (pin "5") (pinfunction "ADJ_5") (pintype "bidirectional"))
      (node (ref "R3") (pin "2") (pinfunction "2_2") (pintype "passive"))
      (node (ref "R4") (pin "2") (pinfunction "2_2") (pintype "passive"))
    )
    (net (code "53") (name "Net-(IC5A-O)") (class "Default")
      (node (ref "IC5") (pin "2") (pinfunction "O_2") (pintype "output"))
      (node (ref "U3") (pin "2") (pinfunction "CS_2") (pintype "bidirectional"))
    )
    (net (code "54") (name "Net-(IC5B-O)") (class "Default")
      (node (ref "IC5") (pin "4") (pinfunction "O_4") (pintype "output"))
      (node (ref "U3") (pin "3") (pinfunction "DI_3") (pintype "bidirectional"))
    )
    (net (code "55") (name "Net-(IC5C-O)") (class "Default")
      (node (ref "IC5") (pin "6") (pinfunction "O_6") (pintype "output"))
      (node (ref "U3") (pin "5") (pinfunction "SCK_5") (pintype "bidirectional"))
    )
    (net (code "56") (name "Net-(IC6-X0)") (class "Default")
      (node (ref "IC6") (pin "12") (pinfunction "X0_12") (pintype "bidirectional"))
      (node (ref "MD1") (pin "1") (pinfunction "+5V_1") (pintype "power_in"))
    )
    (net (code "57") (name "Net-(IC6-Y0)") (class "Default")
      (node (ref "IC6") (pin "2") (pinfunction "Y0_2") (pintype "bidirectional"))
      (node (ref "MD1") (pin "2") (pinfunction "-5V_2") (pintype "power_in"))
    )
    (net (code "58") (name "Net-(IC6-Z0)") (class "Default")
      (node (ref "IC6") (pin "5") (pinfunction "Z0_5") (pintype "bidirectional"))
      (node (ref "MD1") (pin "6") (pinfunction "GND_6") (pintype "bidirectional"))
    )
    (net (code "59") (name "Net-(IC7-X0)") (class "Default")
      (node (ref "IC7") (pin "12") (pinfunction "X0_12") (pintype "bidirectional"))
      (node (ref "MD2") (pin "1") (pinfunction "+5V_1") (pintype "power_in"))
    )
    (net (code "60") (name "Net-(IC7-Y0)") (class "Default")
      (node (ref "IC7") (pin "2") (pinfunction "Y0_2") (pintype "bidirectional"))
      (node (ref "MD2") (pin "2") (pinfunction "-5V_2") (pintype "power_in"))
    )
    (net (code "61") (name "Net-(IC7-Z0)") (class "Default")
      (node (ref "IC7") (pin "5") (pinfunction "Z0_5") (pintype "bidirectional"))
      (node (ref "MD2") (pin "6") (pinfunction "GND_6") (pintype "bidirectional"))
    )
    (net (code "62") (name "Net-(IC8-X0)") (class "Default")
      (node (ref "IC8") (pin "12") (pinfunction "X0_12") (pintype "bidirectional"))
      (node (ref "MD3") (pin "1") (pinfunction "+5V_1") (pintype "power_in"))
    )
    (net (code "63") (name "Net-(IC8-Y0)") (class "Default")
      (node (ref "IC8") (pin "2") (pinfunction "Y0_2") (pintype "bidirectional"))
      (node (ref "MD3") (pin "2") (pinfunction "-5V_2") (pintype "power_in"))
    )
    (net (code "64") (name "Net-(IC8-Z0)") (class "Default")
      (node (ref "IC8") (pin "5") (pinfunction "Z0_5") (pintype "bidirectional"))
      (node (ref "MD3") (pin "6") (pinfunction "GND_6") (pintype "bidirectional"))
    )
    (net (code "65") (name "Net-(IC10A-IN-)") (class "Default")
      (node (ref "C27") (pin "1") (pinfunction "1_1") (pintype "passive"))
      (node (ref "IC10") (pin "1") (pinfunction "OUT_1") (pintype "output"))
      (node (ref "IC10") (pin "2") (pinfunction "IN-_2") (pintype "input"))
      (node (ref "R7") (pin "2") (pinfunction "2_2") (pintype "passive"))
    )
    (net (code "66") (name "Net-(IC10B-IN-)") (class "Default")
      (node (ref "IC10") (pin "6") (pinfunction "IN-_6") (pintype "input"))
      (node (ref "R12") (pin "1") (pinfunction "1_1") (pintype "passive"))
      (node (ref "R7") (pin "1") (pinfunction "1_1") (pintype "passive"))
      (node (ref "R9") (pin "1") (pinfunction "1_1") (pintype "passive"))
    )
    (net (code "67") (name "Net-(IC11-CON)") (class "Default")
      (node (ref "C29") (pin "1") (pinfunction "1_1") (pintype "passive"))
      (node (ref "IC11") (pin "5") (pinfunction "CON_5") (pintype "input"))
    )
    (net (code "68") (name "Net-(IC12-IN+)") (class "Default")
      (node (ref "C28") (pin "1") (pinfunction "1_1") (pintype "passive"))
      (node (ref "IC12") (pin "3") (pinfunction "IN+_3") (pintype "input"))
      (node (ref "R6") (pin "2") (pinfunction "2_2") (pintype "passive"))
    )
    (net (code "69") (name "Net-(IC12-IN-)") (class "Default")
      (node (ref "C30") (pin "1") (pinfunction "1_1") (pintype "passive"))
      (node (ref "IC12") (pin "2") (pinfunction "IN-_2") (pintype "input"))
      (node (ref "R10") (pin "2") (pinfunction "S_2") (pintype "passive"))
    )
    (net (code "70") (name "Net-(IC12-OUT)") (class "Default")
      (node (ref "C30") (pin "2") (pinfunction "2_2") (pintype "passive"))
      (node (ref "IC12") (pin "6") (pinfunction "OUT_6") (pintype "output"))
      (node (ref "R11") (pin "2") (pinfunction "2_2") (pintype "passive"))
      (node (ref "R13") (pin "2") (pinfunction "2_2") (pintype "passive"))
    )
    (net (code "71") (name "Net-(IC13-IN-)") (class "Default")
      (node (ref "IC13") (pin "2") (pinfunction "IN-_2") (pintype "input"))
      (node (ref "R13") (pin "1") (pinfunction "1_1") (pintype "passive"))
      (node (ref "R14") (pin "1") (pinfunction "1_1") (pintype "passive"))
      (node (ref "R15") (pin "1") (pinfunction "1_1") (pintype "passive"))
    )
    (net (code "72") (name "Net-(J1-OUT)") (class "Default")
      (node (ref "J1") (pin "S") (pinfunction "OUT_S") (pintype "bidirectional"))
      (node (ref "MD1") (pin "4") (pinfunction "PR+_4") (pintype "bidirectional"))
    )
    (net (code "73") (name "Net-(J2-OUT)") (class "Default")
      (node (ref "J2") (pin "S") (pinfunction "OUT_S") (pintype "bidirectional"))
      (node (ref "MD2") (pin "4") (pinfunction "PR+_4") (pintype "bidirectional"))
    )
    (net (code "74") (name "Net-(J3-OUT)") (class "Default")
      (node (ref "J3") (pin "S") (pinfunction "OUT_S") (pintype "bidirectional"))
      (node (ref "MD3") (pin "4") (pinfunction "PR+_4") (pintype "bidirectional"))
    )
    (net (code "75") (name "Net-(MD1-PR-)") (class "Default")
      (node (ref "J1") (pin "GND") (pinfunction "GND_GND") (pintype "bidirectional"))
      (node (ref "MD1") (pin "5") (pinfunction "PR-_5") (pintype "input"))
    )
    (net (code "76") (name "Net-(MD2-PR-)") (class "Default")
      (node (ref "J2") (pin "GND") (pinfunction "GND_GND") (pintype "bidirectional"))
      (node (ref "MD2") (pin "5") (pinfunction "PR-_5") (pintype "input"))
    )
    (net (code "77") (name "Net-(MD3-PR-)") (class "Default")
      (node (ref "J3") (pin "GND") (pinfunction "GND_GND") (pintype "bidirectional"))
      (node (ref "MD3") (pin "5") (pinfunction "PR-_5") (pintype "input"))
    )
    (net (code "78") (name "Net-(R10-A)") (class "Default")
      (node (ref "R10") (pin "1") (pinfunction "A_1") (pintype "passive"))
      (node (ref "R11") (pin "1") (pinfunction "1_1") (pintype "passive"))
    )
    (net (code "79") (name "Net-(R10-E)") (class "Default")
      (node (ref "R10") (pin "3") (pinfunction "E_3") (pintype "passive"))
      (node (ref "R8") (pin "1") (pinfunction "1_1") (pintype "passive"))
    )
    (net (code "80") (name "Net-(U2-CAP)") (class "Default")
      (node (ref "C18") (pin "1") (pinfunction "1_1") (pintype "passive"))
      (node (ref "U2") (pin "2") (pinfunction "CAP_2") (pintype "power_in"))
    )
    (net (code "81") (name "unconnected-(IC1-SPK+-Pad3)") (class "Default")
      (node (ref "IC1") (pin "3") (pinfunction "SPK+_3") (pintype "bidirectional"))
    )
    (net (code "82") (name "unconnected-(IC1-SPK--Pad4)") (class "Default")
      (node (ref "IC1") (pin "4") (pinfunction "SPK-_4") (pintype "bidirectional"))
    )
    (net (code "83") (name "unconnected-(IC2-OSC-Pad7)") (class "Default")
      (node (ref "IC2") (pin "7") (pinfunction "OSC_7") (pintype "input"))
    )
    (net (code "84") (name "unconnected-(IC3-Y2-Pad15)") (class "Default")
      (node (ref "IC3") (pin "15") (pinfunction "Y2_15") (pintype "bidirectional"))
    )
    (net (code "85") (name "unconnected-(IC6-X1-Pad13)") (class "Default")
      (node (ref "IC6") (pin "13") (pinfunction "X1_13") (pintype "bidirectional"))
    )
    (net (code "86") (name "unconnected-(IC6-Y1-Pad1)") (class "Default")
      (node (ref "IC6") (pin "1") (pinfunction "Y1_1") (pintype "bidirectional"))
    )
    (net (code "87") (name "unconnected-(IC6-Z1-Pad3)") (class "Default")
      (node (ref "IC6") (pin "3") (pinfunction "Z1_3") (pintype "bidirectional"))
    )
    (net (code "88") (name "unconnected-(IC7-X1-Pad13)") (class "Default")
      (node (ref "IC7") (pin "13") (pinfunction "X1_13") (pintype "bidirectional"))
    )
    (net (code "89") (name "unconnected-(IC7-Y1-Pad1)") (class "Default")
      (node (ref "IC7") (pin "1") (pinfunction "Y1_1") (pintype "bidirectional"))
    )
    (net (code "90") (name "unconnected-(IC7-Z1-Pad3)") (class "Default")
      (node (ref "IC7") (pin "3") (pinfunction "Z1_3") (pintype "bidirectional"))
    )
    (net (code "91") (name "unconnected-(IC8-X1-Pad13)") (class "Default")
      (node (ref "IC8") (pin "13") (pinfunction "X1_13") (pintype "bidirectional"))
    )
    (net (code "92") (name "unconnected-(IC8-Y1-Pad1)") (class "Default")
      (node (ref "IC8") (pin "1") (pinfunction "Y1_1") (pintype "bidirectional"))
    )
    (net (code "93") (name "unconnected-(IC8-Z1-Pad3)") (class "Default")
      (node (ref "IC8") (pin "3") (pinfunction "Z1_3") (pintype "bidirectional"))
    )
    (net (code "94") (name "unconnected-(IC11-DIS-Pad7)") (class "Default")
      (node (ref "IC11") (pin "7") (pinfunction "DIS_7") (pintype "input"))
    )
    (net (code "95") (name "unconnected-(MD5--5V-Pad2)") (class "Default")
      (node (ref "MD5") (pin "2") (pinfunction "-5V_2") (pintype "power_in"))
    )
    (net (code "96") (name "unconnected-(U1-0(RX0)-Pad0)") (class "Default")
      (node (ref "U1") (pin "0") (pinfunction "0(RX0)_0") (pintype "bidirectional"))
    )
    (net (code "97") (name "unconnected-(U1-1(TX0)-Pad1)") (class "Default")
      (node (ref "U1") (pin "1") (pinfunction "1(TX0)_1") (pintype "bidirectional"))
    )
    (net (code "98") (name "unconnected-(U1-18(TX1)-Pad18)") (class "Default")
      (node (ref "U1") (pin "18") (pinfunction "18(TX1)_18") (pintype "bidirectional"))
    )
    (net (code "99") (name "unconnected-(U1-19(RX1)-Pad19)") (class "Default")
      (node (ref "U1") (pin "19") (pinfunction "19(RX1)_19") (pintype "bidirectional"))
    )
    (net (code "100") (name "unconnected-(U1-20(SDA)-Pad20)") (class "Default")
      (node (ref "U1") (pin "20") (pinfunction "20(SDA)_20") (pintype "bidirectional"))
    )
    (net (code "101") (name "unconnected-(U1-21(SCL)-Pad21)") (class "Default")
      (node (ref "U1") (pin "21") (pinfunction "21(SCL)_21") (pintype "bidirectional"))
    )
    (net (code "102") (name "unconnected-(U1-A0(RX0)-PadA0)") (class "Default")
      (node (ref "U1") (pin "A0") (pinfunction "A0(RX0)_A0") (pintype "bidirectional"))
    )
    (net (code "103") (name "unconnected-(U1-A1(TX0)-PadA1)") (class "Default")
      (node (ref "U1") (pin "A1") (pinfunction "A1(TX0)_A1") (pintype "bidirectional"))
    )
    (net (code "104") (name "unconnected-(U1-Pad3)") (class "Default")
      (node (ref "U1") (pin "3") (pinfunction "3_3") (pintype "bidirectional"))
    )
    (net (code "105") (name "unconnected-(U1-Pad4)") (class "Default")
      (node (ref "U1") (pin "4") (pinfunction "4_4") (pintype "bidirectional"))
    )
    (net (code "106") (name "unconnected-(U1-Pad5)") (class "Default")
      (node (ref "U1") (pin "5") (pinfunction "5_5") (pintype "bidirectional"))
    )
    (net (code "107") (name "unconnected-(U1-Pad6)") (class "Default")
      (node (ref "U1") (pin "6") (pinfunction "6_6") (pintype "bidirectional"))
    )
    (net (code "108") (name "unconnected-(U1-Pad8)") (class "Default")
      (node (ref "U1") (pin "8") (pinfunction "8_8") (pintype "bidirectional"))
    )
    (net (code "109") (name "unconnected-(U1-Pad9)") (class "Default")
      (node (ref "U1") (pin "9") (pinfunction "9_9") (pintype "bidirectional"))
    )
    (net (code "110") (name "unconnected-(U1-Pad22)") (class "Default")
      (node (ref "U1") (pin "22") (pinfunction "22_22") (pintype "bidirectional"))
    )
    (net (code "111") (name "unconnected-(U1-Pad23)") (class "Default")
      (node (ref "U1") (pin "23") (pinfunction "23_23") (pintype "bidirectional"))
    )
    (net (code "112") (name "unconnected-(U1-Pad24)") (class "Default")
      (node (ref "U1") (pin "24") (pinfunction "24_24") (pintype "bidirectional"))
    )
    (net (code "113") (name "unconnected-(U1-Pad25)") (class "Default")
      (node (ref "U1") (pin "25") (pinfunction "25_25") (pintype "bidirectional"))
    )
    (net (code "114") (name "unconnected-(U1-Pad26)") (class "Default")
      (node (ref "U1") (pin "26") (pinfunction "26_26") (pintype "bidirectional"))
    )
    (net (code "115") (name "unconnected-(U1-Pad27)") (class "Default")
      (node (ref "U1") (pin "27") (pinfunction "27_27") (pintype "bidirectional"))
    )
    (net (code "116") (name "unconnected-(U1-Pad28)") (class "Default")
      (node (ref "U1") (pin "28") (pinfunction "28_28") (pintype "bidirectional"))
    )
    (net (code "117") (name "unconnected-(U1-Pad29)") (class "Default")
      (node (ref "U1") (pin "29") (pinfunction "29_29") (pintype "bidirectional"))
    )
    (net (code "118") (name "unconnected-(U1-Pad30)") (class "Default")
      (node (ref "U1") (pin "30") (pinfunction "30_30") (pintype "bidirectional"))
    )
    (net (code "119") (name "unconnected-(U1-Pad31)") (class "Default")
      (node (ref "U1") (pin "31") (pinfunction "31_31") (pintype "bidirectional"))
    )
    (net (code "120") (name "unconnected-(U1-Pad32)") (class "Default")
      (node (ref "U1") (pin "32") (pinfunction "32_32") (pintype "bidirectional"))
    )
    (net (code "121") (name "unconnected-(U1-Pad33)") (class "Default")
      (node (ref "U1") (pin "33") (pinfunction "33_33") (pintype "bidirectional"))
    )
    (net (code "122") (name "unconnected-(U1-Pad34)") (class "Default")
      (node (ref "U1") (pin "34") (pinfunction "34_34") (pintype "bidirectional"))
    )
    (net (code "123") (name "unconnected-(U1-Pad35)") (class "Default")
      (node (ref "U1") (pin "35") (pinfunction "35_35") (pintype "bidirectional"))
    )
    (net (code "124") (name "unconnected-(U1-Pad36)") (class "Default")
      (node (ref "U1") (pin "36") (pinfunction "36_36") (pintype "bidirectional"))
    )
    (net (code "125") (name "unconnected-(U1-Pad37)") (class "Default")
      (node (ref "U1") (pin "37") (pinfunction "37_37") (pintype "bidirectional"))
    )
    (net (code "126") (name "unconnected-(U1-Pad38)") (class "Default")
      (node (ref "U1") (pin "38") (pinfunction "38_38") (pintype "bidirectional"))
    )
    (net (code "127") (name "unconnected-(U1-Pad39)") (class "Default")
      (node (ref "U1") (pin "39") (pinfunction "39_39") (pintype "bidirectional"))
    )
    (net (code "128") (name "unconnected-(U1-Pad41)") (class "Default")
      (node (ref "U1") (pin "41") (pinfunction "41_41") (pintype "bidirectional"))
    )
    (net (code "129") (name "unconnected-(U1-Pad46)") (class "Default")
      (node (ref "U1") (pin "46") (pinfunction "46_46") (pintype "bidirectional"))
    )
    (net (code "130") (name "unconnected-(U1-Pad48)") (class "Default")
      (node (ref "U1") (pin "48") (pinfunction "48_48") (pintype "bidirectional"))
    )
    (net (code "131") (name "unconnected-(U1-PadA2)") (class "Default")
      (node (ref "U1") (pin "A2") (pinfunction "A2_A2") (pintype "bidirectional"))
    )
    (net (code "132") (name "unconnected-(U1-PadA3)") (class "Default")
      (node (ref "U1") (pin "A3") (pinfunction "A3_A3") (pintype "bidirectional"))
    )
    (net (code "133") (name "unconnected-(U1-PadA4)") (class "Default")
      (node (ref "U1") (pin "A4") (pinfunction "A4_A4") (pintype "bidirectional"))
    )
    (net (code "134") (name "unconnected-(U1-PadA8)") (class "Default")
      (node (ref "U1") (pin "A8") (pinfunction "A8_A8") (pintype "bidirectional"))
    )
    (net (code "135") (name "unconnected-(U1-PadA9)") (class "Default")
      (node (ref "U1") (pin "A9") (pinfunction "A9_A9") (pintype "bidirectional"))
    )
    (net (code "136") (name "unconnected-(U1-PadAREF)") (class "Default")
      (node (ref "U1") (pin "AREF") (pinfunction "AREF_AREF") (pintype "bidirectional"))
    )
    (net (code "137") (name "unconnected-(U1-PadIOREF)") (class "Default")
      (node (ref "U1") (pin "IOREF") (pinfunction "IOREF_IOREF") (pintype "bidirectional"))
    )
    (net (code "138") (name "unconnected-(U1-PadRESET)") (class "Default")
      (node (ref "U1") (pin "RESET") (pinfunction "RESET_RESET") (pintype "bidirectional"))
    )
    (net (code "139") (name "unconnected-(U2-INT1-Pad6)") (class "Default")
      (node (ref "U2") (pin "6") (pinfunction "INT1_6") (pintype "output"))
    )
    (net (code "140") (name "unconnected-(U2-INT2-Pad5)") (class "Default")
      (node (ref "U2") (pin "5") (pinfunction "INT2_5") (pintype "output"))
    )
    (net (code "141") (name "unconnected-(U3-NC-Pad1)") (class "Default")
      (node (ref "U3") (pin "1") (pinfunction "NC_1") (pintype "bidirectional"))
    )
    (net (code "142") (name "unconnected-(U3-RSV-Pad8)") (class "Default")
      (node (ref "U3") (pin "8") (pinfunction "RSV_8") (pintype "bidirectional"))
    )
  )
)
